# Power.net
KiCad netlist of a schematic drawn in Altium Designer
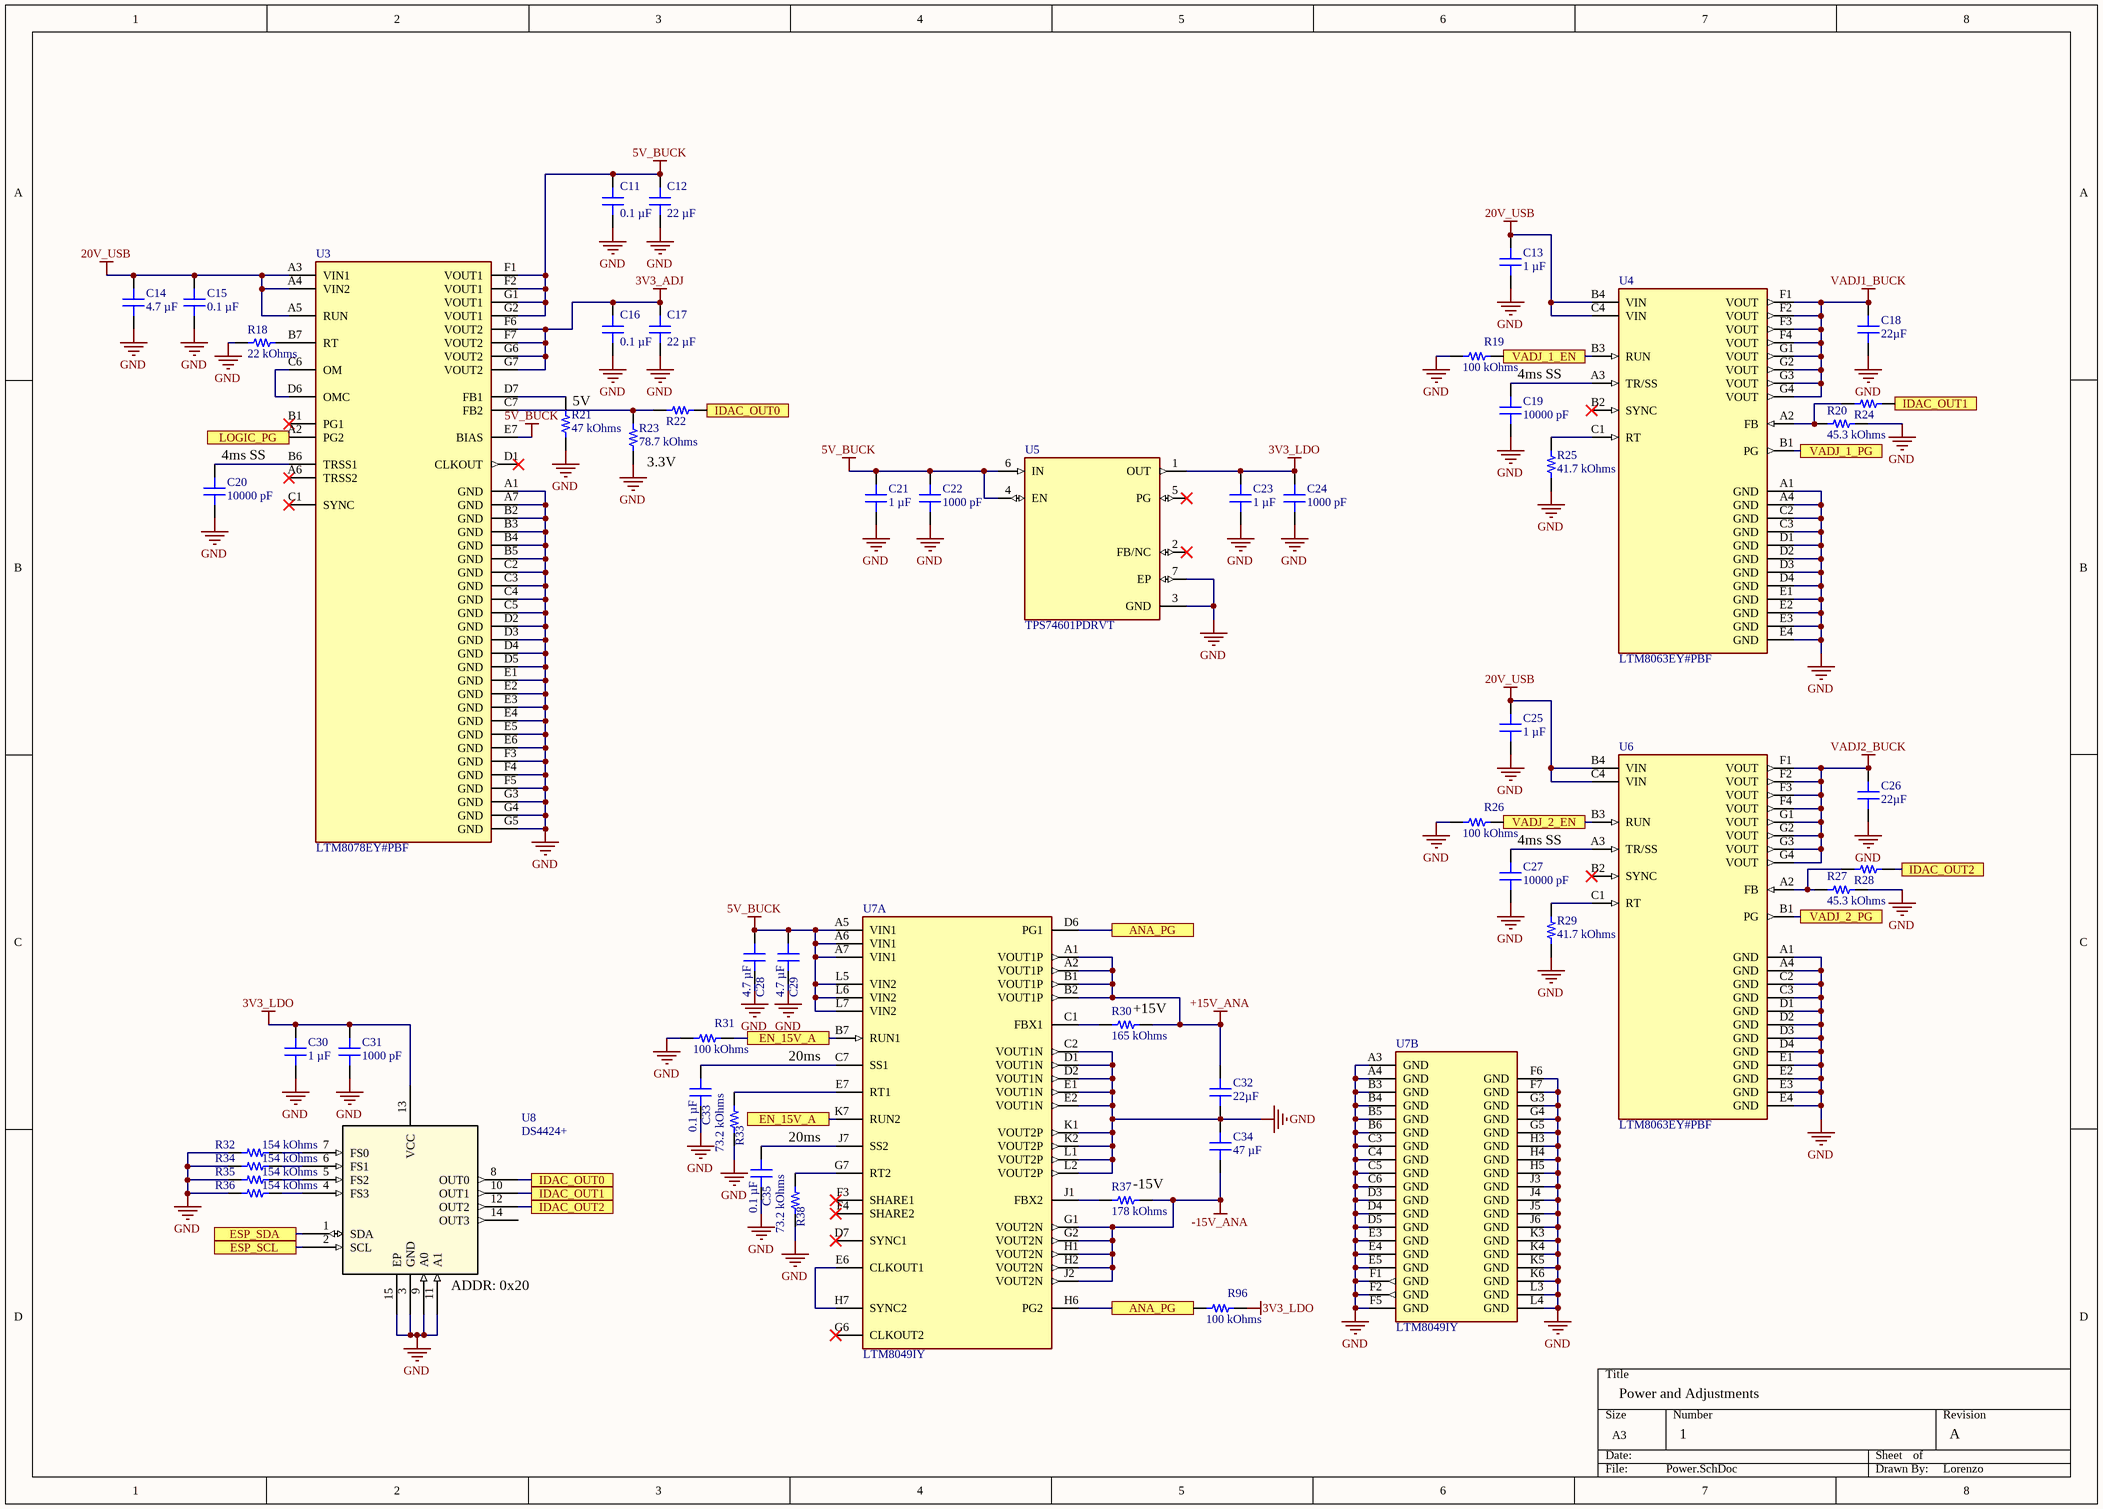
[diagram p0: Power.SchDoc]

(export (version "E")
  (design (tool "Eeschema 10.0.6"))
  (components
    (comp (ref "C11")
      (value "0.1 µF")
      (footprint "CAP 0603_1608")
      (description "CAP CER 0.1UF 50V X7R 0603")
      (fields
        (field (name "PART NUMBER") "CGA3E2X7R1H104M080AE")
        (field (name "MANUFACTURER") "TDK Corporation")
      )
      (libsource (lib "Altium Database Library V2 Local") (part "Capacitor"))
    )
    (comp (ref "C12")
      (value "22 µF")
      (footprint "CAP 0603_1608")
      (description "CAP CER 22UF 6.3V X6S 0603")
      (fields (field (name "PART NUMBER") "CC0603MRX6S5BB226") (field (name "MANUFACTURER") "Yageo"))
      (libsource (lib "Altium Database Library V2 Local") (part "Capacitor"))
    )
    (comp (ref "C13")
      (value "1 µF")
      (footprint "CAP 0603_1608")
      (description "CAP CER 1UF 50V X5R 0603")
      (fields
        (field (name "PART NUMBER") "C1608X5R1H105K080AB")
        (field (name "MANUFACTURER") "TDK Corporation")
      )
      (libsource (lib "Altium Database Library V2 Local") (part "Capacitor"))
    )
    (comp (ref "C14")
      (value "4.7 µF")
      (footprint "CAP 0603_1608")
      (description "CAP CER 4.7UF 25V X5R 0603")
      (fields
        (field (name "PART NUMBER") "GRM188R61E475ME11J")
        (field (name "MANUFACTURER") "Murata Electronics")
      )
      (libsource (lib "Altium Database Library V2 Local") (part "Capacitor"))
    )
    (comp (ref "C15")
      (value "0.1 µF")
      (footprint "CAP 0603_1608")
      (description "CAP CER 0.1UF 50V X7R 0603")
      (fields
        (field (name "PART NUMBER") "CGA3E2X7R1H104M080AE")
        (field (name "MANUFACTURER") "TDK Corporation")
      )
      (libsource (lib "Altium Database Library V2 Local") (part "Capacitor"))
    )
    (comp (ref "C16")
      (value "0.1 µF")
      (footprint "CAP 0603_1608")
      (description "CAP CER 0.1UF 50V X7R 0603")
      (fields
        (field (name "PART NUMBER") "CGA3E2X7R1H104M080AE")
        (field (name "MANUFACTURER") "TDK Corporation")
      )
      (libsource (lib "Altium Database Library V2 Local") (part "Capacitor"))
    )
    (comp (ref "C17")
      (value "22 µF")
      (footprint "CAP 0603_1608")
      (description "CAP CER 22UF 6.3V X6S 0603")
      (fields (field (name "PART NUMBER") "CC0603MRX6S5BB226") (field (name "MANUFACTURER") "Yageo"))
      (libsource (lib "Altium Database Library V2 Local") (part "Capacitor"))
    )
    (comp (ref "C18")
      (value "22µF")
      (footprint "CAP 1210_3225 - 2.8MM")
      (description "CAP CER 22UF 25V X7R 1210")
      (fields (field (name "PART NUMBER") "12103C226KAT2A") (field (name "MANUFACTURER") "AVX Corporation"))
      (libsource (lib "Altium Database Library V2 Local") (part "Capacitor"))
    )
    (comp (ref "C19")
      (value "10000 pF")
      (footprint "CAP 0603_1608")
      (description "CAP CER 10000PF 50V X7R 0603")
      (fields (field (name "PART NUMBER") "C0603X103K5RAC7867") (field (name "MANUFACTURER") "KEMET"))
      (libsource (lib "Altium Database Library V2 Local") (part "Capacitor"))
    )
    (comp (ref "C20")
      (value "10000 pF")
      (footprint "CAP 0603_1608")
      (description "CAP CER 10000PF 50V X7R 0603")
      (fields (field (name "PART NUMBER") "C0603X103K5RAC7867") (field (name "MANUFACTURER") "KEMET"))
      (libsource (lib "Altium Database Library V2 Local") (part "Capacitor"))
    )
    (comp (ref "C21")
      (value "1 µF")
      (footprint "CAP 0603_1608")
      (description "CAP CER 1UF 50V X5R 0603")
      (fields
        (field (name "PART NUMBER") "C1608X5R1H105K080AB")
        (field (name "MANUFACTURER") "TDK Corporation")
      )
      (libsource (lib "Altium Database Library V2 Local") (part "Capacitor"))
    )
    (comp (ref "C22")
      (value "1000 pF")
      (footprint "CAP 0603_1608")
      (description "CAP CER 1000PF 25V C0G/NPO 0603")
      (fields (field (name "PART NUMBER") "CC0603GRNPO8BN102") (field (name "MANUFACTURER") "Yageo"))
      (libsource (lib "Altium Database Library V2 Local") (part "Capacitor"))
    )
    (comp (ref "C23")
      (value "1 µF")
      (footprint "CAP 0603_1608")
      (description "CAP CER 1UF 50V X5R 0603")
      (fields
        (field (name "PART NUMBER") "C1608X5R1H105K080AB")
        (field (name "MANUFACTURER") "TDK Corporation")
      )
      (libsource (lib "Altium Database Library V2 Local") (part "Capacitor"))
    )
    (comp (ref "C24")
      (value "1000 pF")
      (footprint "CAP 0603_1608")
      (description "CAP CER 1000PF 25V C0G/NPO 0603")
      (fields (field (name "PART NUMBER") "CC0603GRNPO8BN102") (field (name "MANUFACTURER") "Yageo"))
      (libsource (lib "Altium Database Library V2 Local") (part "Capacitor"))
    )
    (comp (ref "C25")
      (value "1 µF")
      (footprint "CAP 0603_1608")
      (description "CAP CER 1UF 50V X5R 0603")
      (fields
        (field (name "PART NUMBER") "C1608X5R1H105K080AB")
        (field (name "MANUFACTURER") "TDK Corporation")
      )
      (libsource (lib "Altium Database Library V2 Local") (part "Capacitor"))
    )
    (comp (ref "C26")
      (value "22µF")
      (footprint "CAP 1210_3225 - 2.8MM")
      (description "CAP CER 22UF 25V X7R 1210")
      (fields (field (name "PART NUMBER") "12103C226KAT2A") (field (name "MANUFACTURER") "AVX Corporation"))
      (libsource (lib "Altium Database Library V2 Local") (part "Capacitor"))
    )
    (comp (ref "C27")
      (value "10000 pF")
      (footprint "CAP 0603_1608")
      (description "CAP CER 10000PF 50V X7R 0603")
      (fields (field (name "PART NUMBER") "C0603X103K5RAC7867") (field (name "MANUFACTURER") "KEMET"))
      (libsource (lib "Altium Database Library V2 Local") (part "Capacitor"))
    )
    (comp (ref "C28")
      (value "4.7 µF")
      (footprint "CAP 0603_1608")
      (description "CAP CER 4.7UF 25V X5R 0603")
      (fields
        (field (name "PART NUMBER") "GRM188R61E475ME11J")
        (field (name "MANUFACTURER") "Murata Electronics")
      )
      (libsource (lib "Altium Database Library V2 Local") (part "Capacitor"))
    )
    (comp (ref "C29")
      (value "4.7 µF")
      (footprint "CAP 0603_1608")
      (description "CAP CER 4.7UF 25V X5R 0603")
      (fields
        (field (name "PART NUMBER") "GRM188R61E475ME11J")
        (field (name "MANUFACTURER") "Murata Electronics")
      )
      (libsource (lib "Altium Database Library V2 Local") (part "Capacitor"))
    )
    (comp (ref "C30")
      (value "1 µF")
      (footprint "CAP 0603_1608")
      (description "CAP CER 1UF 50V X5R 0603")
      (fields
        (field (name "PART NUMBER") "C1608X5R1H105K080AB")
        (field (name "MANUFACTURER") "TDK Corporation")
      )
      (libsource (lib "Altium Database Library V2 Local") (part "Capacitor"))
    )
    (comp (ref "C31")
      (value "1000 pF")
      (footprint "CAP 0603_1608")
      (description "CAP CER 1000PF 25V C0G/NPO 0603")
      (fields (field (name "PART NUMBER") "CC0603GRNPO8BN102") (field (name "MANUFACTURER") "Yageo"))
      (libsource (lib "Altium Database Library V2 Local") (part "Capacitor"))
    )
    (comp (ref "C32")
      (value "22µF")
      (footprint "CAP 1210_3225 - 2.8MM")
      (description "CAP CER 22UF 25V X7R 1210")
      (fields (field (name "PART NUMBER") "12103C226KAT2A") (field (name "MANUFACTURER") "AVX Corporation"))
      (libsource (lib "Altium Database Library V2 Local") (part "Capacitor"))
    )
    (comp (ref "C33")
      (value "0.1 µF")
      (footprint "CAP 0603_1608")
      (description "CAP CER 0.1UF 50V X7R 0603")
      (fields
        (field (name "PART NUMBER") "CGA3E2X7R1H104M080AE")
        (field (name "MANUFACTURER") "TDK Corporation")
      )
      (libsource (lib "Altium Database Library V2 Local") (part "Capacitor"))
    )
    (comp (ref "C34")
      (value "47 µF")
      (footprint "CAP 1210_3225 - 1MM")
      (description "CAP CER 47UF 25V X5R 1210")
      (fields (field (name "PART NUMBER") "KGM32LR51E476MU") (field (name "MANUFACTURER") "KYOCERA AVX"))
      (libsource (lib "Altium Database Library V2 Local") (part "Capacitor"))
    )
    (comp (ref "C35")
      (value "0.1 µF")
      (footprint "CAP 0603_1608")
      (description "CAP CER 0.1UF 50V X7R 0603")
      (fields
        (field (name "PART NUMBER") "CGA3E2X7R1H104M080AE")
        (field (name "MANUFACTURER") "TDK Corporation")
      )
      (libsource (lib "Altium Database Library V2 Local") (part "Capacitor"))
    )
    (comp (ref "R18")
      (value "22 kOhms")
      (footprint "RES 0603_1608")
      (description "RES SMD 22K OHM 1% 1/10W 0603")
      (fields (field (name "PART NUMBER") "KTR03EZPF2202") (field (name "MANUFACTURER") "Rohm Semiconductor"))
      (libsource (lib "Altium Database Library V2 Local") (part "Resistor"))
    )
    (comp (ref "R19")
      (value "100 kOhms")
      (footprint "RES 0603_1608")
      (description "RES 100K OHM 1% 1/3W 0603")
      (fields
        (field (name "PART NUMBER") "SG73P1JTTD1003F")
        (field (name "MANUFACTURER") "KOA Speer Electronics, Inc.")
      )
      (libsource (lib "Altium Database Library V2 Local") (part "Resistor"))
    )
    (comp (ref "R20")
      (value "45.3 kOhms")
      (footprint "RES 0603_1608")
      (description "RES SMD 45.3K OHM 1% 1/10W 0603")
      (fields (field (name "PART NUMBER") "AC0603FR-0745K3L") (field (name "MANUFACTURER") "Yageo"))
      (libsource (lib "Altium Database Library V2 Local") (part "Resistor"))
    )
    (comp (ref "R21")
      (value "47 kOhms")
      (footprint "RES 0603_1608")
      (description "RES SMD 47K OHM 1% 1/10W 0603")
      (fields (field (name "PART NUMBER") "RCA060347K0FKEA") (field (name "MANUFACTURER") "Vishay Dale"))
      (libsource (lib "Altium Database Library V2 Local") (part "Resistor"))
    )
    (comp (ref "R22")
      (value "~")
      (footprint "RES 0603_1608")
      (description "RES 0 OHM JUMPER 1/8W 0603")
      (fields
        (field (name "PART NUMBER") "MCT0603MZ0000ZP500")
        (field (name "MANUFACTURER") "Vishay Beyschlag")
      )
      (libsource (lib "Altium Database Library V2 Local") (part "Resistor"))
    )
    (comp (ref "R23")
      (value "78.7 kOhms")
      (footprint "RES 0603_1608")
      (description "RES SMD 78.7K OHM 1% 1/16W 0603")
      (fields
        (field (name "PART NUMBER") "CPF0603F78K7C1")
        (field (name "MANUFACTURER") "TE Connectivity Passive Product")
      )
      (libsource (lib "Altium Database Library V2 Local") (part "Resistor"))
    )
    (comp (ref "R24")
      (value "~")
      (footprint "RES 0603_1608")
      (description "RES 0 OHM JUMPER 1/8W 0603")
      (fields
        (field (name "PART NUMBER") "MCT0603MZ0000ZP500")
        (field (name "MANUFACTURER") "Vishay Beyschlag")
      )
      (libsource (lib "Altium Database Library V2 Local") (part "Resistor"))
    )
    (comp (ref "R25")
      (value "41.7 kOhms")
      (footprint "RES 0603_1608")
      (description "RES 41.7K OHM 1% 1/10W 0603")
      (fields
        (field (name "PART NUMBER") "RN73R1JTTD4172F10")
        (field (name "MANUFACTURER") "KOA Speer Electronics, Inc.")
      )
      (libsource (lib "Altium Database Library V2 Local") (part "Resistor"))
    )
    (comp (ref "R26")
      (value "100 kOhms")
      (footprint "RES 0603_1608")
      (description "RES 100K OHM 1% 1/3W 0603")
      (fields
        (field (name "PART NUMBER") "SG73P1JTTD1003F")
        (field (name "MANUFACTURER") "KOA Speer Electronics, Inc.")
      )
      (libsource (lib "Altium Database Library V2 Local") (part "Resistor"))
    )
    (comp (ref "R27")
      (value "45.3 kOhms")
      (footprint "RES 0603_1608")
      (description "RES SMD 45.3K OHM 1% 1/10W 0603")
      (fields (field (name "PART NUMBER") "AC0603FR-0745K3L") (field (name "MANUFACTURER") "Yageo"))
      (libsource (lib "Altium Database Library V2 Local") (part "Resistor"))
    )
    (comp (ref "R28")
      (value "~")
      (footprint "RES 0603_1608")
      (description "RES 0 OHM JUMPER 1/8W 0603")
      (fields
        (field (name "PART NUMBER") "MCT0603MZ0000ZP500")
        (field (name "MANUFACTURER") "Vishay Beyschlag")
      )
      (libsource (lib "Altium Database Library V2 Local") (part "Resistor"))
    )
    (comp (ref "R29")
      (value "41.7 kOhms")
      (footprint "RES 0603_1608")
      (description "RES 41.7K OHM 1% 1/10W 0603")
      (fields
        (field (name "PART NUMBER") "RN73R1JTTD4172F10")
        (field (name "MANUFACTURER") "KOA Speer Electronics, Inc.")
      )
      (libsource (lib "Altium Database Library V2 Local") (part "Resistor"))
    )
    (comp (ref "R30")
      (value "165 kOhms")
      (footprint "RES 0603_1608")
      (description "RES 165K OHM 1% 1/10W 0603")
      (fields (field (name "PART NUMBER") "RC0603FR-07165KL") (field (name "MANUFACTURER") "Yageo"))
      (libsource (lib "Altium Database Library V2 Local") (part "Resistor"))
    )
    (comp (ref "R31")
      (value "100 kOhms")
      (footprint "RES 0603_1608")
      (description "RES 100K OHM 1% 1/3W 0603")
      (fields
        (field (name "PART NUMBER") "SG73P1JTTD1003F")
        (field (name "MANUFACTURER") "KOA Speer Electronics, Inc.")
      )
      (libsource (lib "Altium Database Library V2 Local") (part "Resistor"))
    )
    (comp (ref "R32")
      (value "154 kOhms")
      (footprint "RES 0603_1608")
      (description "RES SMD 154K OHM 1% 1/10W 0603")
      (fields (field (name "PART NUMBER") "AC0603FR-07154KL") (field (name "MANUFACTURER") "Yageo"))
      (libsource (lib "Altium Database Library V2 Local") (part "Resistor"))
    )
    (comp (ref "R33")
      (value "73.2 kOhms")
      (footprint "RES 0603_1608")
      (description "RES 73.2K OHM 1% 1/10W 0603")
      (fields (field (name "PART NUMBER") "RC0603FR-0773K2L") (field (name "MANUFACTURER") "Yageo"))
      (libsource (lib "Altium Database Library V2 Local") (part "Resistor"))
    )
    (comp (ref "R34")
      (value "154 kOhms")
      (footprint "RES 0603_1608")
      (description "RES SMD 154K OHM 1% 1/10W 0603")
      (fields (field (name "PART NUMBER") "AC0603FR-07154KL") (field (name "MANUFACTURER") "Yageo"))
      (libsource (lib "Altium Database Library V2 Local") (part "Resistor"))
    )
    (comp (ref "R35")
      (value "154 kOhms")
      (footprint "RES 0603_1608")
      (description "RES SMD 154K OHM 1% 1/10W 0603")
      (fields (field (name "PART NUMBER") "AC0603FR-07154KL") (field (name "MANUFACTURER") "Yageo"))
      (libsource (lib "Altium Database Library V2 Local") (part "Resistor"))
    )
    (comp (ref "R36")
      (value "154 kOhms")
      (footprint "RES 0603_1608")
      (description "RES SMD 154K OHM 1% 1/10W 0603")
      (fields (field (name "PART NUMBER") "AC0603FR-07154KL") (field (name "MANUFACTURER") "Yageo"))
      (libsource (lib "Altium Database Library V2 Local") (part "Resistor"))
    )
    (comp (ref "R37")
      (value "178 kOhms")
      (footprint "RES 0603_1608")
      (description "RES 178K OHM 1% 1/10W 0603")
      (fields
        (field (name "PART NUMBER") "RK73H1JTTD1783F")
        (field (name "MANUFACTURER") "KOA Speer Electronics, Inc.")
      )
      (libsource (lib "Altium Database Library V2 Local") (part "Resistor"))
    )
    (comp (ref "R38")
      (value "73.2 kOhms")
      (footprint "RES 0603_1608")
      (description "RES 73.2K OHM 1% 1/10W 0603")
      (fields (field (name "PART NUMBER") "RC0603FR-0773K2L") (field (name "MANUFACTURER") "Yageo"))
      (libsource (lib "Altium Database Library V2 Local") (part "Resistor"))
    )
    (comp (ref "R96")
      (value "100 kOhms")
      (footprint "RES 0603_1608")
      (description "RES 100K OHM 1% 1/3W 0603")
      (fields
        (field (name "PART NUMBER") "SG73P1JTTD1003F")
        (field (name "MANUFACTURER") "KOA Speer Electronics, Inc.")
      )
      (libsource (lib "Altium Database Library V2 Local") (part "Resistor"))
    )
    (comp (ref "U3")
      (value "LTM8078EY#PBF")
      (footprint "FP-BGA-49-05-08-1518-IPC_C")
      (description "DUAL 40VIN, 3A SILENT SWITCR UMO")
      (libsource (lib "Altium Content Vault") (part "4060324c9a51752e3d8da8510a218c1"))
    )
    (comp (ref "U4")
      (value "LTM8063EY#PBF")
      (footprint "FP-BGA-28-05-08-1517-MFG")
      (description "DC DC CONVERTER 0.8-15V")
      (fields
        (field (name "OCTOPART") "https://octopart.com/ltm8063ey%23pbf-analog+devices-88947122")
        (field (name "MANUFACTURER") "Analog Devices")
      )
      (libsource (lib "Altium Content Vault") (part "b54610757978533170b9aabd89f6d2c"))
    )
    (comp (ref "U5")
      (value "TPS74601PDRVT")
      (footprint "SON65P200X200X80-7N")
      (fields (field (name "MF") "Texas Instruments"))
      (libsource (lib "Lib") (part "TPS74601PDRVT"))
    )
    (comp (ref "U6")
      (value "LTM8063EY#PBF")
      (footprint "FP-BGA-28-05-08-1517-MFG")
      (description "DC DC CONVERTER 0.8-15V")
      (fields
        (field (name "OCTOPART") "https://octopart.com/ltm8063ey%23pbf-analog+devices-88947122")
        (field (name "MANUFACTURER") "Analog Devices")
      )
      (libsource (lib "Altium Content Vault") (part "b54610757978533170b9aabd89f6d2c"))
    )
    (comp (ref "U7")
      (value "LTM8049IY")
      (footprint "FP-BGA-77-05-08-1964-MFG")
      (description "DC DC CONVERTER +/-2.5 TO +/-24V")
      (libsource (lib "Altium Content Vault") (part "11cd7d106844afe49abc479e229d0be"))
    )
    (comp (ref "U8")
      (value "DS4424+")
      (footprint "21-0137_T1433+2_MXM")
      (description "Two-/Four-Channel, IÂ²C, 7-Bit Sink/Source Current DAC")
      (fields
        (field (name "MANUFACTURER_PART_NUMBER") "ds4424n+")
        (field (name "COPYRIGHT") "Copyright (C) 2026 Ultra Librarian. All rights reserved.")
      )
      (libsource (lib "Lib") (part "DS4424"))
    )
  )
  (nets
    (net (code "1") (name "+15V_ANA") (class "Default")
      (node (ref "C32") (pin "2") (pinfunction "2_2") (pintype "passive"))
      (node (ref "R30") (pin "2") (pinfunction "2_2") (pintype "passive"))
      (node (ref "U7") (pin "A1") (pinfunction "VOUT1P_A1") (pintype "output"))
      (node (ref "U7") (pin "A2") (pinfunction "VOUT1P_A2") (pintype "output"))
      (node (ref "U7") (pin "B1") (pinfunction "VOUT1P_B1") (pintype "output"))
      (node (ref "U7") (pin "B2") (pinfunction "VOUT1P_B2") (pintype "output"))
    )
    (net (code "2") (name "-15V_ANA") (class "Default")
      (node (ref "C34") (pin "1") (pinfunction "1_1") (pintype "passive"))
      (node (ref "R37") (pin "2") (pinfunction "2_2") (pintype "passive"))
      (node (ref "U7") (pin "G1") (pinfunction "VOUT2N_G1") (pintype "output"))
      (node (ref "U7") (pin "G2") (pinfunction "VOUT2N_G2") (pintype "output"))
      (node (ref "U7") (pin "H1") (pinfunction "VOUT2N_H1") (pintype "output"))
      (node (ref "U7") (pin "H2") (pinfunction "VOUT2N_H2") (pintype "output"))
      (node (ref "U7") (pin "J2") (pinfunction "VOUT2N_J2") (pintype "output"))
    )
    (net (code "3") (name "/ANA_PG") (class "Default")
      (node (ref "R96") (pin "1") (pinfunction "1_1") (pintype "passive"))
      (node (ref "U7") (pin "D6") (pinfunction "PG1_D6") (pintype "passive"))
      (node (ref "U7") (pin "H6") (pinfunction "PG2_H6") (pintype "passive"))
    )
    (net (code "4") (name "/EN_15V_A") (class "Default")
      (node (ref "R31") (pin "2") (pinfunction "2_2") (pintype "passive"))
      (node (ref "U7") (pin "B7") (pinfunction "RUN1_B7") (pintype "input"))
      (node (ref "U7") (pin "K7") (pinfunction "RUN2_K7") (pintype "passive"))
    )
    (net (code "5") (name "/ESP_SCL") (class "Default")
      (node (ref "U8") (pin "2") (pinfunction "SCL_2") (pintype "input"))
    )
    (net (code "6") (name "/ESP_SDA") (class "Default")
      (node (ref "U8") (pin "1") (pinfunction "SDA_1") (pintype "bidirectional"))
    )
    (net (code "7") (name "/IDAC_OUT0") (class "Default")
      (node (ref "R22") (pin "2") (pinfunction "2_2") (pintype "passive"))
      (node (ref "U8") (pin "8") (pinfunction "OUT0_8") (pintype "output"))
    )
    (net (code "8") (name "/IDAC_OUT1") (class "Default")
      (node (ref "R24") (pin "2") (pinfunction "2_2") (pintype "passive"))
      (node (ref "U8") (pin "10") (pinfunction "OUT1_10") (pintype "output"))
    )
    (net (code "9") (name "/IDAC_OUT2") (class "Default")
      (node (ref "R28") (pin "2") (pinfunction "2_2") (pintype "passive"))
      (node (ref "U8") (pin "12") (pinfunction "OUT2_12") (pintype "output"))
    )
    (net (code "10") (name "/LOGIC_PG") (class "Default")
      (node (ref "U3") (pin "A2") (pinfunction "PG2_A2") (pintype "open_collector"))
    )
    (net (code "11") (name "/VADJ_1_EN") (class "Default")
      (node (ref "R19") (pin "2") (pinfunction "2_2") (pintype "passive"))
      (node (ref "U4") (pin "B3") (pinfunction "RUN_B3") (pintype "input"))
    )
    (net (code "12") (name "/VADJ_1_PG") (class "Default")
      (node (ref "U4") (pin "B1") (pinfunction "PG_B1") (pintype "output"))
    )
    (net (code "13") (name "/VADJ_2_EN") (class "Default")
      (node (ref "R26") (pin "2") (pinfunction "2_2") (pintype "passive"))
      (node (ref "U6") (pin "B3") (pinfunction "RUN_B3") (pintype "input"))
    )
    (net (code "14") (name "/VADJ_2_PG") (class "Default")
      (node (ref "U6") (pin "B1") (pinfunction "PG_B1") (pintype "output"))
    )
    (net (code "15") (name "3V3_ADJ") (class "Default")
      (node (ref "C16") (pin "2") (pinfunction "2_2") (pintype "passive"))
      (node (ref "C17") (pin "2") (pinfunction "2_2") (pintype "passive"))
      (node (ref "U3") (pin "F6") (pinfunction "VOUT2_F6") (pintype "power_in"))
      (node (ref "U3") (pin "F7") (pinfunction "VOUT2_F7") (pintype "power_in"))
      (node (ref "U3") (pin "G6") (pinfunction "VOUT2_G6") (pintype "power_in"))
      (node (ref "U3") (pin "G7") (pinfunction "VOUT2_G7") (pintype "power_in"))
    )
    (net (code "16") (name "3V3_LDO") (class "Default")
      (node (ref "C23") (pin "2") (pinfunction "2_2") (pintype "passive"))
      (node (ref "C24") (pin "2") (pinfunction "2_2") (pintype "passive"))
      (node (ref "C30") (pin "2") (pinfunction "2_2") (pintype "passive"))
      (node (ref "C31") (pin "2") (pinfunction "2_2") (pintype "passive"))
      (node (ref "R96") (pin "2") (pinfunction "2_2") (pintype "passive"))
      (node (ref "U5") (pin "1") (pinfunction "OUT_1") (pintype "output"))
      (node (ref "U8") (pin "13") (pinfunction "VCC_13") (pintype "power_in"))
    )
    (net (code "17") (name "5V_BUCK") (class "Default")
      (node (ref "C11") (pin "2") (pinfunction "2_2") (pintype "passive"))
      (node (ref "C12") (pin "2") (pinfunction "2_2") (pintype "passive"))
      (node (ref "C21") (pin "2") (pinfunction "2_2") (pintype "passive"))
      (node (ref "C22") (pin "2") (pinfunction "2_2") (pintype "passive"))
      (node (ref "C28") (pin "2") (pinfunction "2_2") (pintype "passive"))
      (node (ref "C29") (pin "2") (pinfunction "2_2") (pintype "passive"))
      (node (ref "U3") (pin "E7") (pinfunction "BIAS_E7") (pintype "passive"))
      (node (ref "U3") (pin "F1") (pinfunction "VOUT1_F1") (pintype "power_in"))
      (node (ref "U3") (pin "F2") (pinfunction "VOUT1_F2") (pintype "power_in"))
      (node (ref "U3") (pin "G1") (pinfunction "VOUT1_G1") (pintype "power_in"))
      (node (ref "U3") (pin "G2") (pinfunction "VOUT1_G2") (pintype "power_in"))
      (node (ref "U5") (pin "4") (pinfunction "EN_4") (pintype "bidirectional"))
      (node (ref "U5") (pin "6") (pinfunction "IN_6") (pintype "input"))
      (node (ref "U7") (pin "A5") (pinfunction "VIN1_A5") (pintype "power_in"))
      (node (ref "U7") (pin "A6") (pinfunction "VIN1_A6") (pintype "power_in"))
      (node (ref "U7") (pin "A7") (pinfunction "VIN1_A7") (pintype "power_in"))
      (node (ref "U7") (pin "L5") (pinfunction "VIN2_L5") (pintype "power_in"))
      (node (ref "U7") (pin "L6") (pinfunction "VIN2_L6") (pintype "power_in"))
      (node (ref "U7") (pin "L7") (pinfunction "VIN2_L7") (pintype "power_in"))
    )
    (net (code "18") (name "20V_USB") (class "Default")
      (node (ref "C13") (pin "2") (pinfunction "2_2") (pintype "passive"))
      (node (ref "C14") (pin "2") (pinfunction "2_2") (pintype "passive"))
      (node (ref "C15") (pin "2") (pinfunction "2_2") (pintype "passive"))
      (node (ref "C25") (pin "2") (pinfunction "2_2") (pintype "passive"))
      (node (ref "U3") (pin "A3") (pinfunction "VIN1_A3") (pintype "power_in"))
      (node (ref "U3") (pin "A4") (pinfunction "VIN2_A4") (pintype "power_in"))
      (node (ref "U3") (pin "A5") (pinfunction "RUN_A5") (pintype "passive"))
      (node (ref "U4") (pin "B4") (pinfunction "VIN_B4") (pintype "power_in"))
      (node (ref "U4") (pin "C4") (pinfunction "VIN_C4") (pintype "power_in"))
      (node (ref "U6") (pin "B4") (pinfunction "VIN_B4") (pintype "power_in"))
      (node (ref "U6") (pin "C4") (pinfunction "VIN_C4") (pintype "power_in"))
    )
    (net (code "19") (name "GND") (class "Default")
      (node (ref "C11") (pin "1") (pinfunction "1_1") (pintype "passive"))
      (node (ref "C12") (pin "1") (pinfunction "1_1") (pintype "passive"))
      (node (ref "C13") (pin "1") (pinfunction "1_1") (pintype "passive"))
      (node (ref "C14") (pin "1") (pinfunction "1_1") (pintype "passive"))
      (node (ref "C15") (pin "1") (pinfunction "1_1") (pintype "passive"))
      (node (ref "C16") (pin "1") (pinfunction "1_1") (pintype "passive"))
      (node (ref "C17") (pin "1") (pinfunction "1_1") (pintype "passive"))
      (node (ref "C18") (pin "1") (pinfunction "1_1") (pintype "passive"))
      (node (ref "C19") (pin "1") (pinfunction "1_1") (pintype "passive"))
      (node (ref "C20") (pin "1") (pinfunction "1_1") (pintype "passive"))
      (node (ref "C21") (pin "1") (pinfunction "1_1") (pintype "passive"))
      (node (ref "C22") (pin "1") (pinfunction "1_1") (pintype "passive"))
      (node (ref "C23") (pin "1") (pinfunction "1_1") (pintype "passive"))
      (node (ref "C24") (pin "1") (pinfunction "1_1") (pintype "passive"))
      (node (ref "C25") (pin "1") (pinfunction "1_1") (pintype "passive"))
      (node (ref "C26") (pin "1") (pinfunction "1_1") (pintype "passive"))
      (node (ref "C27") (pin "1") (pinfunction "1_1") (pintype "passive"))
      (node (ref "C28") (pin "1") (pinfunction "1_1") (pintype "passive"))
      (node (ref "C29") (pin "1") (pinfunction "1_1") (pintype "passive"))
      (node (ref "C30") (pin "1") (pinfunction "1_1") (pintype "passive"))
      (node (ref "C31") (pin "1") (pinfunction "1_1") (pintype "passive"))
      (node (ref "C32") (pin "1") (pinfunction "1_1") (pintype "passive"))
      (node (ref "C33") (pin "1") (pinfunction "1_1") (pintype "passive"))
      (node (ref "C34") (pin "2") (pinfunction "2_2") (pintype "passive"))
      (node (ref "C35") (pin "1") (pinfunction "1_1") (pintype "passive"))
      (node (ref "R18") (pin "1") (pinfunction "1_1") (pintype "passive"))
      (node (ref "R19") (pin "1") (pinfunction "1_1") (pintype "passive"))
      (node (ref "R20") (pin "1") (pinfunction "1_1") (pintype "passive"))
      (node (ref "R21") (pin "1") (pinfunction "1_1") (pintype "passive"))
      (node (ref "R23") (pin "1") (pinfunction "1_1") (pintype "passive"))
      (node (ref "R25") (pin "1") (pinfunction "1_1") (pintype "passive"))
      (node (ref "R26") (pin "1") (pinfunction "1_1") (pintype "passive"))
      (node (ref "R27") (pin "1") (pinfunction "1_1") (pintype "passive"))
      (node (ref "R29") (pin "1") (pinfunction "1_1") (pintype "passive"))
      (node (ref "R31") (pin "1") (pinfunction "1_1") (pintype "passive"))
      (node (ref "R32") (pin "1") (pinfunction "1_1") (pintype "passive"))
      (node (ref "R33") (pin "1") (pinfunction "1_1") (pintype "passive"))
      (node (ref "R34") (pin "1") (pinfunction "1_1") (pintype "passive"))
      (node (ref "R35") (pin "1") (pinfunction "1_1") (pintype "passive"))
      (node (ref "R36") (pin "1") (pinfunction "1_1") (pintype "passive"))
      (node (ref "R38") (pin "1") (pinfunction "1_1") (pintype "passive"))
      (node (ref "U3") (pin "A1") (pinfunction "GND_A1") (pintype "power_in"))
      (node (ref "U3") (pin "A7") (pinfunction "GND_A7") (pintype "power_in"))
      (node (ref "U3") (pin "B2") (pinfunction "GND_B2") (pintype "power_in"))
      (node (ref "U3") (pin "B3") (pinfunction "GND_B3") (pintype "power_in"))
      (node (ref "U3") (pin "B4") (pinfunction "GND_B4") (pintype "power_in"))
      (node (ref "U3") (pin "B5") (pinfunction "GND_B5") (pintype "power_in"))
      (node (ref "U3") (pin "C2") (pinfunction "GND_C2") (pintype "power_in"))
      (node (ref "U3") (pin "C3") (pinfunction "GND_C3") (pintype "power_in"))
      (node (ref "U3") (pin "C4") (pinfunction "GND_C4") (pintype "power_in"))
      (node (ref "U3") (pin "C5") (pinfunction "GND_C5") (pintype "power_in"))
      (node (ref "U3") (pin "D2") (pinfunction "GND_D2") (pintype "power_in"))
      (node (ref "U3") (pin "D3") (pinfunction "GND_D3") (pintype "power_in"))
      (node (ref "U3") (pin "D4") (pinfunction "GND_D4") (pintype "power_in"))
      (node (ref "U3") (pin "D5") (pinfunction "GND_D5") (pintype "power_in"))
      (node (ref "U3") (pin "E1") (pinfunction "GND_E1") (pintype "power_in"))
      (node (ref "U3") (pin "E2") (pinfunction "GND_E2") (pintype "power_in"))
      (node (ref "U3") (pin "E3") (pinfunction "GND_E3") (pintype "power_in"))
      (node (ref "U3") (pin "E4") (pinfunction "GND_E4") (pintype "power_in"))
      (node (ref "U3") (pin "E5") (pinfunction "GND_E5") (pintype "power_in"))
      (node (ref "U3") (pin "E6") (pinfunction "GND_E6") (pintype "power_in"))
      (node (ref "U3") (pin "F3") (pinfunction "GND_F3") (pintype "power_in"))
      (node (ref "U3") (pin "F4") (pinfunction "GND_F4") (pintype "power_in"))
      (node (ref "U3") (pin "F5") (pinfunction "GND_F5") (pintype "power_in"))
      (node (ref "U3") (pin "G3") (pinfunction "GND_G3") (pintype "power_in"))
      (node (ref "U3") (pin "G4") (pinfunction "GND_G4") (pintype "power_in"))
      (node (ref "U3") (pin "G5") (pinfunction "GND_G5") (pintype "power_in"))
      (node (ref "U4") (pin "A1") (pinfunction "GND_A1") (pintype "power_in"))
      (node (ref "U4") (pin "A4") (pinfunction "GND_A4") (pintype "power_in"))
      (node (ref "U4") (pin "C2") (pinfunction "GND_C2") (pintype "power_in"))
      (node (ref "U4") (pin "C3") (pinfunction "GND_C3") (pintype "power_in"))
      (node (ref "U4") (pin "D1") (pinfunction "GND_D1") (pintype "power_in"))
      (node (ref "U4") (pin "D2") (pinfunction "GND_D2") (pintype "power_in"))
      (node (ref "U4") (pin "D3") (pinfunction "GND_D3") (pintype "power_in"))
      (node (ref "U4") (pin "D4") (pinfunction "GND_D4") (pintype "power_in"))
      (node (ref "U4") (pin "E1") (pinfunction "GND_E1") (pintype "power_in"))
      (node (ref "U4") (pin "E2") (pinfunction "GND_E2") (pintype "power_in"))
      (node (ref "U4") (pin "E3") (pinfunction "GND_E3") (pintype "power_in"))
      (node (ref "U4") (pin "E4") (pinfunction "GND_E4") (pintype "power_in"))
      (node (ref "U5") (pin "3") (pinfunction "GND_3") (pintype "power_in"))
      (node (ref "U5") (pin "7") (pinfunction "EP_7") (pintype "bidirectional"))
      (node (ref "U6") (pin "A1") (pinfunction "GND_A1") (pintype "power_in"))
      (node (ref "U6") (pin "A4") (pinfunction "GND_A4") (pintype "power_in"))
      (node (ref "U6") (pin "C2") (pinfunction "GND_C2") (pintype "power_in"))
      (node (ref "U6") (pin "C3") (pinfunction "GND_C3") (pintype "power_in"))
      (node (ref "U6") (pin "D1") (pinfunction "GND_D1") (pintype "power_in"))
      (node (ref "U6") (pin "D2") (pinfunction "GND_D2") (pintype "power_in"))
      (node (ref "U6") (pin "D3") (pinfunction "GND_D3") (pintype "power_in"))
      (node (ref "U6") (pin "D4") (pinfunction "GND_D4") (pintype "power_in"))
      (node (ref "U6") (pin "E1") (pinfunction "GND_E1") (pintype "power_in"))
      (node (ref "U6") (pin "E2") (pinfunction "GND_E2") (pintype "power_in"))
      (node (ref "U6") (pin "E3") (pinfunction "GND_E3") (pintype "power_in"))
      (node (ref "U6") (pin "E4") (pinfunction "GND_E4") (pintype "power_in"))
      (node (ref "U7") (pin "A3") (pinfunction "GND_A3") (pintype "power_in"))
      (node (ref "U7") (pin "A4") (pinfunction "GND_A4") (pintype "power_in"))
      (node (ref "U7") (pin "B3") (pinfunction "GND_B3") (pintype "power_in"))
      (node (ref "U7") (pin "B4") (pinfunction "GND_B4") (pintype "power_in"))
      (node (ref "U7") (pin "B5") (pinfunction "GND_B5") (pintype "power_in"))
      (node (ref "U7") (pin "B6") (pinfunction "GND_B6") (pintype "power_in"))
      (node (ref "U7") (pin "C2") (pinfunction "VOUT1N_C2") (pintype "output"))
      (node (ref "U7") (pin "C3") (pinfunction "GND_C3") (pintype "power_in"))
      (node (ref "U7") (pin "C4") (pinfunction "GND_C4") (pintype "power_in"))
      (node (ref "U7") (pin "C5") (pinfunction "GND_C5") (pintype "power_in"))
      (node (ref "U7") (pin "C6") (pinfunction "GND_C6") (pintype "power_in"))
      (node (ref "U7") (pin "D1") (pinfunction "VOUT1N_D1") (pintype "output"))
      (node (ref "U7") (pin "D2") (pinfunction "VOUT1N_D2") (pintype "output"))
      (node (ref "U7") (pin "D3") (pinfunction "GND_D3") (pintype "power_in"))
      (node (ref "U7") (pin "D4") (pinfunction "GND_D4") (pintype "power_in"))
      (node (ref "U7") (pin "D5") (pinfunction "GND_D5") (pintype "power_in"))
      (node (ref "U7") (pin "E1") (pinfunction "VOUT1N_E1") (pintype "output"))
      (node (ref "U7") (pin "E2") (pinfunction "VOUT1N_E2") (pintype "output"))
      (node (ref "U7") (pin "E3") (pinfunction "GND_E3") (pintype "power_in"))
      (node (ref "U7") (pin "E4") (pinfunction "GND_E4") (pintype "power_in"))
      (node (ref "U7") (pin "E5") (pinfunction "GND_E5") (pintype "power_in"))
      (node (ref "U7") (pin "F1") (pinfunction "GND_F1") (pintype "output"))
      (node (ref "U7") (pin "F2") (pinfunction "GND_F2") (pintype "output"))
      (node (ref "U7") (pin "F5") (pinfunction "GND_F5") (pintype "power_in"))
      (node (ref "U7") (pin "F6") (pinfunction "GND_F6") (pintype "power_in"))
      (node (ref "U7") (pin "F7") (pinfunction "GND_F7") (pintype "power_in"))
      (node (ref "U7") (pin "G3") (pinfunction "GND_G3") (pintype "power_in"))
      (node (ref "U7") (pin "G4") (pinfunction "GND_G4") (pintype "power_in"))
      (node (ref "U7") (pin "G5") (pinfunction "GND_G5") (pintype "power_in"))
      (node (ref "U7") (pin "H3") (pinfunction "GND_H3") (pintype "power_in"))
      (node (ref "U7") (pin "H4") (pinfunction "GND_H4") (pintype "power_in"))
      (node (ref "U7") (pin "H5") (pinfunction "GND_H5") (pintype "power_in"))
      (node (ref "U7") (pin "J3") (pinfunction "GND_J3") (pintype "power_in"))
      (node (ref "U7") (pin "J4") (pinfunction "GND_J4") (pintype "power_in"))
      (node (ref "U7") (pin "J5") (pinfunction "GND_J5") (pintype "power_in"))
      (node (ref "U7") (pin "J6") (pinfunction "GND_J6") (pintype "power_in"))
      (node (ref "U7") (pin "K1") (pinfunction "VOUT2P_K1") (pintype "output"))
      (node (ref "U7") (pin "K2") (pinfunction "VOUT2P_K2") (pintype "output"))
      (node (ref "U7") (pin "K3") (pinfunction "GND_K3") (pintype "power_in"))
      (node (ref "U7") (pin "K4") (pinfunction "GND_K4") (pintype "power_in"))
      (node (ref "U7") (pin "K5") (pinfunction "GND_K5") (pintype "power_in"))
      (node (ref "U7") (pin "K6") (pinfunction "GND_K6") (pintype "power_in"))
      (node (ref "U7") (pin "L1") (pinfunction "VOUT2P_L1") (pintype "output"))
      (node (ref "U7") (pin "L2") (pinfunction "VOUT2P_L2") (pintype "output"))
      (node (ref "U7") (pin "L3") (pinfunction "GND_L3") (pintype "power_in"))
      (node (ref "U7") (pin "L4") (pinfunction "GND_L4") (pintype "power_in"))
      (node (ref "U8") (pin "11") (pinfunction "A1_11") (pintype "input"))
      (node (ref "U8") (pin "15") (pinfunction "EP_15") (pintype "passive"))
      (node (ref "U8") (pin "3") (pinfunction "GND_3") (pintype "power_in"))
      (node (ref "U8") (pin "9") (pinfunction "A0_9") (pintype "input"))
    )
    (net (code "20") (name "Net-(U3-FB1)") (class "Default")
      (node (ref "R21") (pin "2") (pinfunction "2_2") (pintype "passive"))
      (node (ref "U3") (pin "D7") (pinfunction "FB1_D7") (pintype "passive"))
    )
    (net (code "21") (name "Net-(U3-FB2)") (class "Default")
      (node (ref "R22") (pin "1") (pinfunction "1_1") (pintype "passive"))
      (node (ref "R23") (pin "2") (pinfunction "2_2") (pintype "passive"))
      (node (ref "U3") (pin "C7") (pinfunction "FB2_C7") (pintype "passive"))
    )
    (net (code "22") (name "Net-(U3-OM)") (class "Default")
      (node (ref "U3") (pin "C6") (pinfunction "OM_C6") (pintype "passive"))
      (node (ref "U3") (pin "D6") (pinfunction "OMC_D6") (pintype "passive"))
    )
    (net (code "23") (name "Net-(U3-RT)") (class "Default")
      (node (ref "R18") (pin "2") (pinfunction "2_2") (pintype "passive"))
      (node (ref "U3") (pin "B7") (pinfunction "RT_B7") (pintype "passive"))
    )
    (net (code "24") (name "Net-(U3-TRSS1)") (class "Default")
      (node (ref "C20") (pin "2") (pinfunction "2_2") (pintype "passive"))
      (node (ref "U3") (pin "B6") (pinfunction "TRSS1_B6") (pintype "passive"))
    )
    (net (code "25") (name "Net-(U4-FB)") (class "Default")
      (node (ref "R20") (pin "2") (pinfunction "2_2") (pintype "passive"))
      (node (ref "R24") (pin "1") (pinfunction "1_1") (pintype "passive"))
      (node (ref "U4") (pin "A2") (pinfunction "FB_A2") (pintype "input"))
    )
    (net (code "26") (name "Net-(U4-RT)") (class "Default")
      (node (ref "R25") (pin "2") (pinfunction "2_2") (pintype "passive"))
      (node (ref "U4") (pin "C1") (pinfunction "RT_C1") (pintype "input"))
    )
    (net (code "27") (name "Net-(U4-TR{slash}SS)") (class "Default")
      (node (ref "C19") (pin "2") (pinfunction "2_2") (pintype "passive"))
      (node (ref "U4") (pin "A3") (pinfunction "TR/SS_A3") (pintype "input"))
    )
    (net (code "28") (name "Net-(U6-FB)") (class "Default")
      (node (ref "R27") (pin "2") (pinfunction "2_2") (pintype "passive"))
      (node (ref "R28") (pin "1") (pinfunction "1_1") (pintype "passive"))
      (node (ref "U6") (pin "A2") (pinfunction "FB_A2") (pintype "input"))
    )
    (net (code "29") (name "Net-(U6-RT)") (class "Default")
      (node (ref "R29") (pin "2") (pinfunction "2_2") (pintype "passive"))
      (node (ref "U6") (pin "C1") (pinfunction "RT_C1") (pintype "input"))
    )
    (net (code "30") (name "Net-(U6-TR{slash}SS)") (class "Default")
      (node (ref "C27") (pin "2") (pinfunction "2_2") (pintype "passive"))
      (node (ref "U6") (pin "A3") (pinfunction "TR/SS_A3") (pintype "input"))
    )
    (net (code "31") (name "Net-(U7A-CLKOUT1)") (class "Default")
      (node (ref "U7") (pin "E6") (pinfunction "CLKOUT1_E6") (pintype "passive"))
      (node (ref "U7") (pin "H7") (pinfunction "SYNC2_H7") (pintype "passive"))
    )
    (net (code "32") (name "Net-(U7A-FBX1)") (class "Default")
      (node (ref "R30") (pin "1") (pinfunction "1_1") (pintype "passive"))
      (node (ref "U7") (pin "C1") (pinfunction "FBX1_C1") (pintype "passive"))
    )
    (net (code "33") (name "Net-(U7A-FBX2)") (class "Default")
      (node (ref "R37") (pin "1") (pinfunction "1_1") (pintype "passive"))
      (node (ref "U7") (pin "J1") (pinfunction "FBX2_J1") (pintype "passive"))
    )
    (net (code "34") (name "Net-(U7A-RT1)") (class "Default")
      (node (ref "R33") (pin "2") (pinfunction "2_2") (pintype "passive"))
      (node (ref "U7") (pin "E7") (pinfunction "RT1_E7") (pintype "passive"))
    )
    (net (code "35") (name "Net-(U7A-RT2)") (class "Default")
      (node (ref "R38") (pin "2") (pinfunction "2_2") (pintype "passive"))
      (node (ref "U7") (pin "G7") (pinfunction "RT2_G7") (pintype "passive"))
    )
    (net (code "36") (name "Net-(U7A-SS1)") (class "Default")
      (node (ref "C33") (pin "2") (pinfunction "2_2") (pintype "passive"))
      (node (ref "U7") (pin "C7") (pinfunction "SS1_C7") (pintype "passive"))
    )
    (net (code "37") (name "Net-(U7A-SS2)") (class "Default")
      (node (ref "C35") (pin "2") (pinfunction "2_2") (pintype "passive"))
      (node (ref "U7") (pin "J7") (pinfunction "SS2_J7") (pintype "passive"))
    )
    (net (code "38") (name "Net-(U8-FS0)") (class "Default")
      (node (ref "R32") (pin "2") (pinfunction "2_2") (pintype "passive"))
      (node (ref "U8") (pin "7") (pinfunction "FS0_7") (pintype "input"))
    )
    (net (code "39") (name "Net-(U8-FS1)") (class "Default")
      (node (ref "R34") (pin "2") (pinfunction "2_2") (pintype "passive"))
      (node (ref "U8") (pin "6") (pinfunction "FS1_6") (pintype "input"))
    )
    (net (code "40") (name "Net-(U8-FS2)") (class "Default")
      (node (ref "R35") (pin "2") (pinfunction "2_2") (pintype "passive"))
      (node (ref "U8") (pin "5") (pinfunction "FS2_5") (pintype "input"))
    )
    (net (code "41") (name "Net-(U8-FS3)") (class "Default")
      (node (ref "R36") (pin "2") (pinfunction "2_2") (pintype "passive"))
      (node (ref "U8") (pin "4") (pinfunction "FS3_4") (pintype "input"))
    )
    (net (code "42") (name "VADJ1_BUCK") (class "Default")
      (node (ref "C18") (pin "2") (pinfunction "2_2") (pintype "passive"))
      (node (ref "U4") (pin "F1") (pinfunction "VOUT_F1") (pintype "output"))
      (node (ref "U4") (pin "F2") (pinfunction "VOUT_F2") (pintype "output"))
      (node (ref "U4") (pin "F3") (pinfunction "VOUT_F3") (pintype "output"))
      (node (ref "U4") (pin "F4") (pinfunction "VOUT_F4") (pintype "output"))
      (node (ref "U4") (pin "G1") (pinfunction "VOUT_G1") (pintype "output"))
      (node (ref "U4") (pin "G2") (pinfunction "VOUT_G2") (pintype "output"))
      (node (ref "U4") (pin "G3") (pinfunction "VOUT_G3") (pintype "output"))
      (node (ref "U4") (pin "G4") (pinfunction "VOUT_G4") (pintype "output"))
    )
    (net (code "43") (name "VADJ2_BUCK") (class "Default")
      (node (ref "C26") (pin "2") (pinfunction "2_2") (pintype "passive"))
      (node (ref "U6") (pin "F1") (pinfunction "VOUT_F1") (pintype "output"))
      (node (ref "U6") (pin "F2") (pinfunction "VOUT_F2") (pintype "output"))
      (node (ref "U6") (pin "F3") (pinfunction "VOUT_F3") (pintype "output"))
      (node (ref "U6") (pin "F4") (pinfunction "VOUT_F4") (pintype "output"))
      (node (ref "U6") (pin "G1") (pinfunction "VOUT_G1") (pintype "output"))
      (node (ref "U6") (pin "G2") (pinfunction "VOUT_G2") (pintype "output"))
      (node (ref "U6") (pin "G3") (pinfunction "VOUT_G3") (pintype "output"))
      (node (ref "U6") (pin "G4") (pinfunction "VOUT_G4") (pintype "output"))
    )
    (net (code "44") (name "unconnected-(U3-CLKOUT-PadD1)") (class "Default")
      (node (ref "U3") (pin "D1") (pinfunction "CLKOUT_D1") (pintype "output+no_connect"))
    )
    (net (code "45") (name "unconnected-(U3-PG1-PadB1)") (class "Default")
      (node (ref "U3") (pin "B1") (pinfunction "PG1_B1") (pintype "open_collector+no_connect"))
    )
    (net (code "46") (name "unconnected-(U3-SYNC-PadC1)") (class "Default")
      (node (ref "U3") (pin "C1") (pinfunction "SYNC_C1") (pintype "passive+no_connect"))
    )
    (net (code "47") (name "unconnected-(U3-TRSS2-PadA6)") (class "Default")
      (node (ref "U3") (pin "A6") (pinfunction "TRSS2_A6") (pintype "passive+no_connect"))
    )
    (net (code "48") (name "unconnected-(U4-SYNC-PadB2)") (class "Default")
      (node (ref "U4") (pin "B2") (pinfunction "SYNC_B2") (pintype "input+no_connect"))
    )
    (net (code "49") (name "unconnected-(U5-FB{slash}NC-Pad2)") (class "Default")
      (node (ref "U5") (pin "2") (pinfunction "FB/NC_2") (pintype "bidirectional+no_connect"))
    )
    (net (code "50") (name "unconnected-(U5-PG-Pad5)") (class "Default")
      (node (ref "U5") (pin "5") (pinfunction "PG_5") (pintype "bidirectional+no_connect"))
    )
    (net (code "51") (name "unconnected-(U6-SYNC-PadB2)") (class "Default")
      (node (ref "U6") (pin "B2") (pinfunction "SYNC_B2") (pintype "input+no_connect"))
    )
    (net (code "52") (name "unconnected-(U7A-CLKOUT2-PadG6)") (class "Default")
      (node (ref "U7") (pin "G6") (pinfunction "CLKOUT2_G6") (pintype "passive+no_connect"))
    )
    (net (code "53") (name "unconnected-(U7A-SHARE1-PadF3)") (class "Default")
      (node (ref "U7") (pin "F3") (pinfunction "SHARE1_F3") (pintype "passive+no_connect"))
    )
    (net (code "54") (name "unconnected-(U7A-SHARE2-PadF4)") (class "Default")
      (node (ref "U7") (pin "F4") (pinfunction "SHARE2_F4") (pintype "passive+no_connect"))
    )
    (net (code "55") (name "unconnected-(U7A-SYNC1-PadD7)") (class "Default")
      (node (ref "U7") (pin "D7") (pinfunction "SYNC1_D7") (pintype "passive+no_connect"))
    )
    (net (code "56") (name "unconnected-(U8-OUT3-Pad14)") (class "Default")
      (node (ref "U8") (pin "14") (pinfunction "OUT3_14") (pintype "output"))
    )
  )
)
